# SCH_Arduino_Nano_ESP32_CapibaraZero_2024.net
KiCad netlist of a schematic drawn in EasyEDA
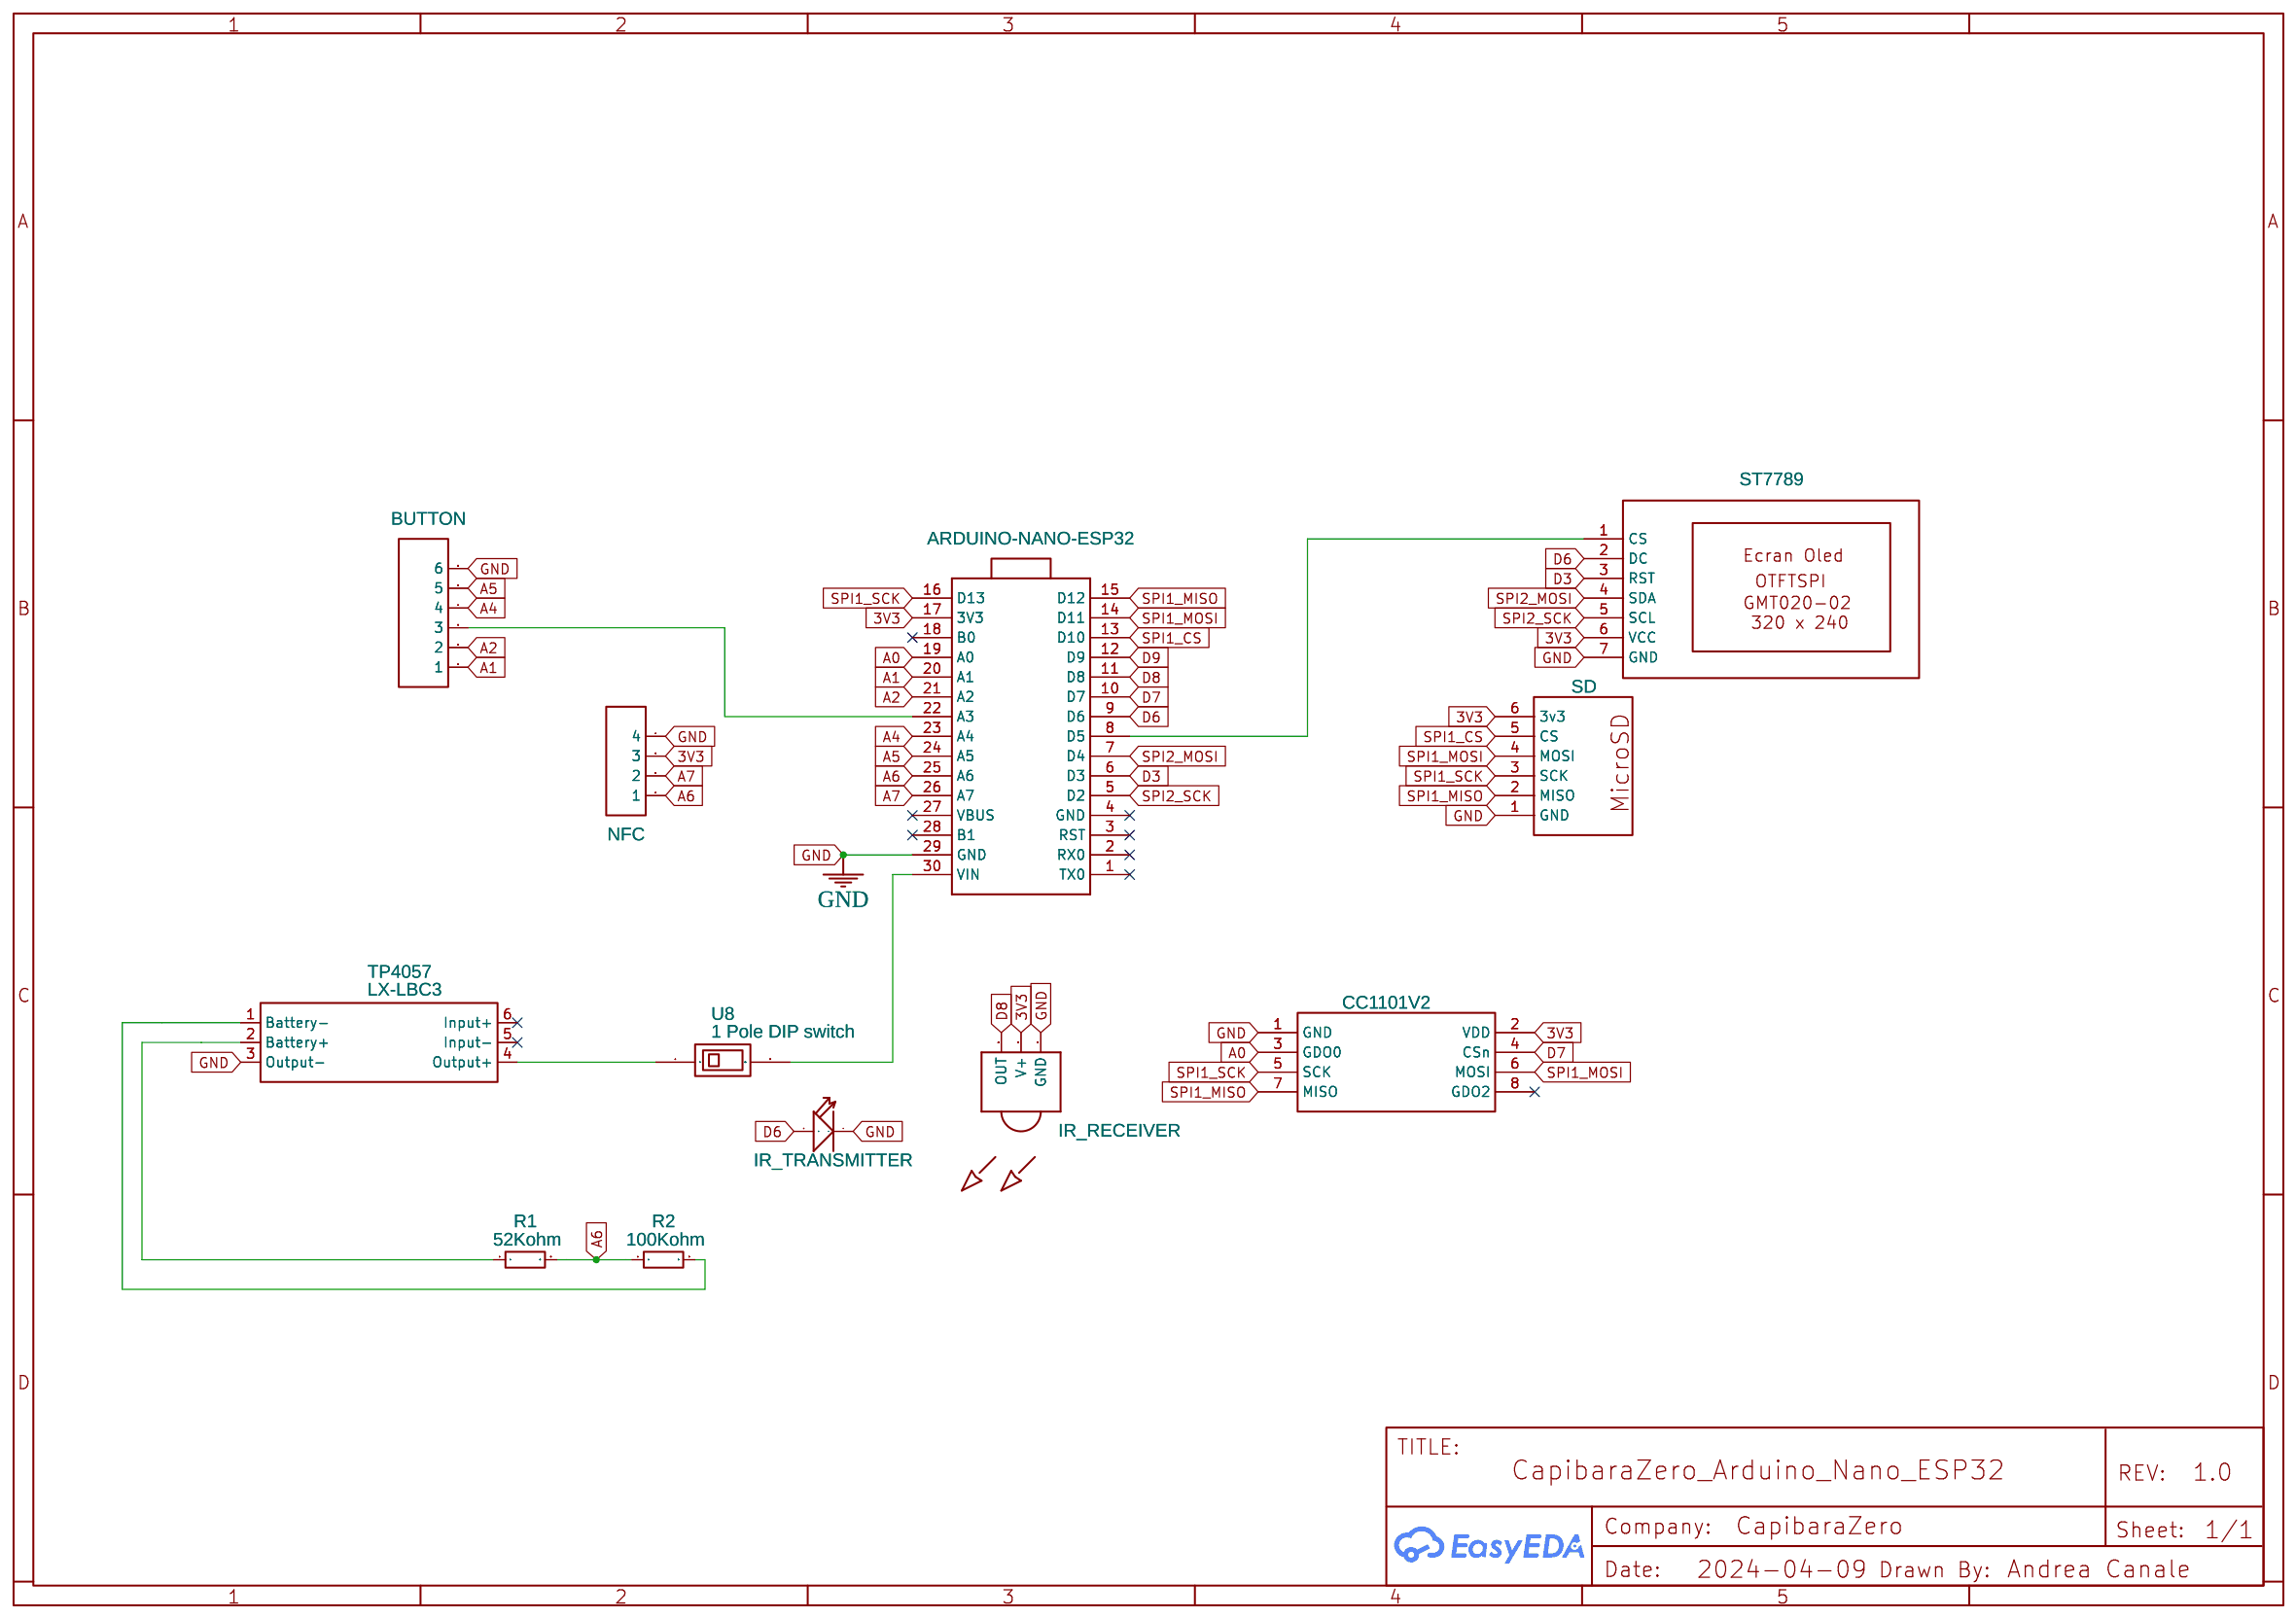
[diagram p0: MainScheme]
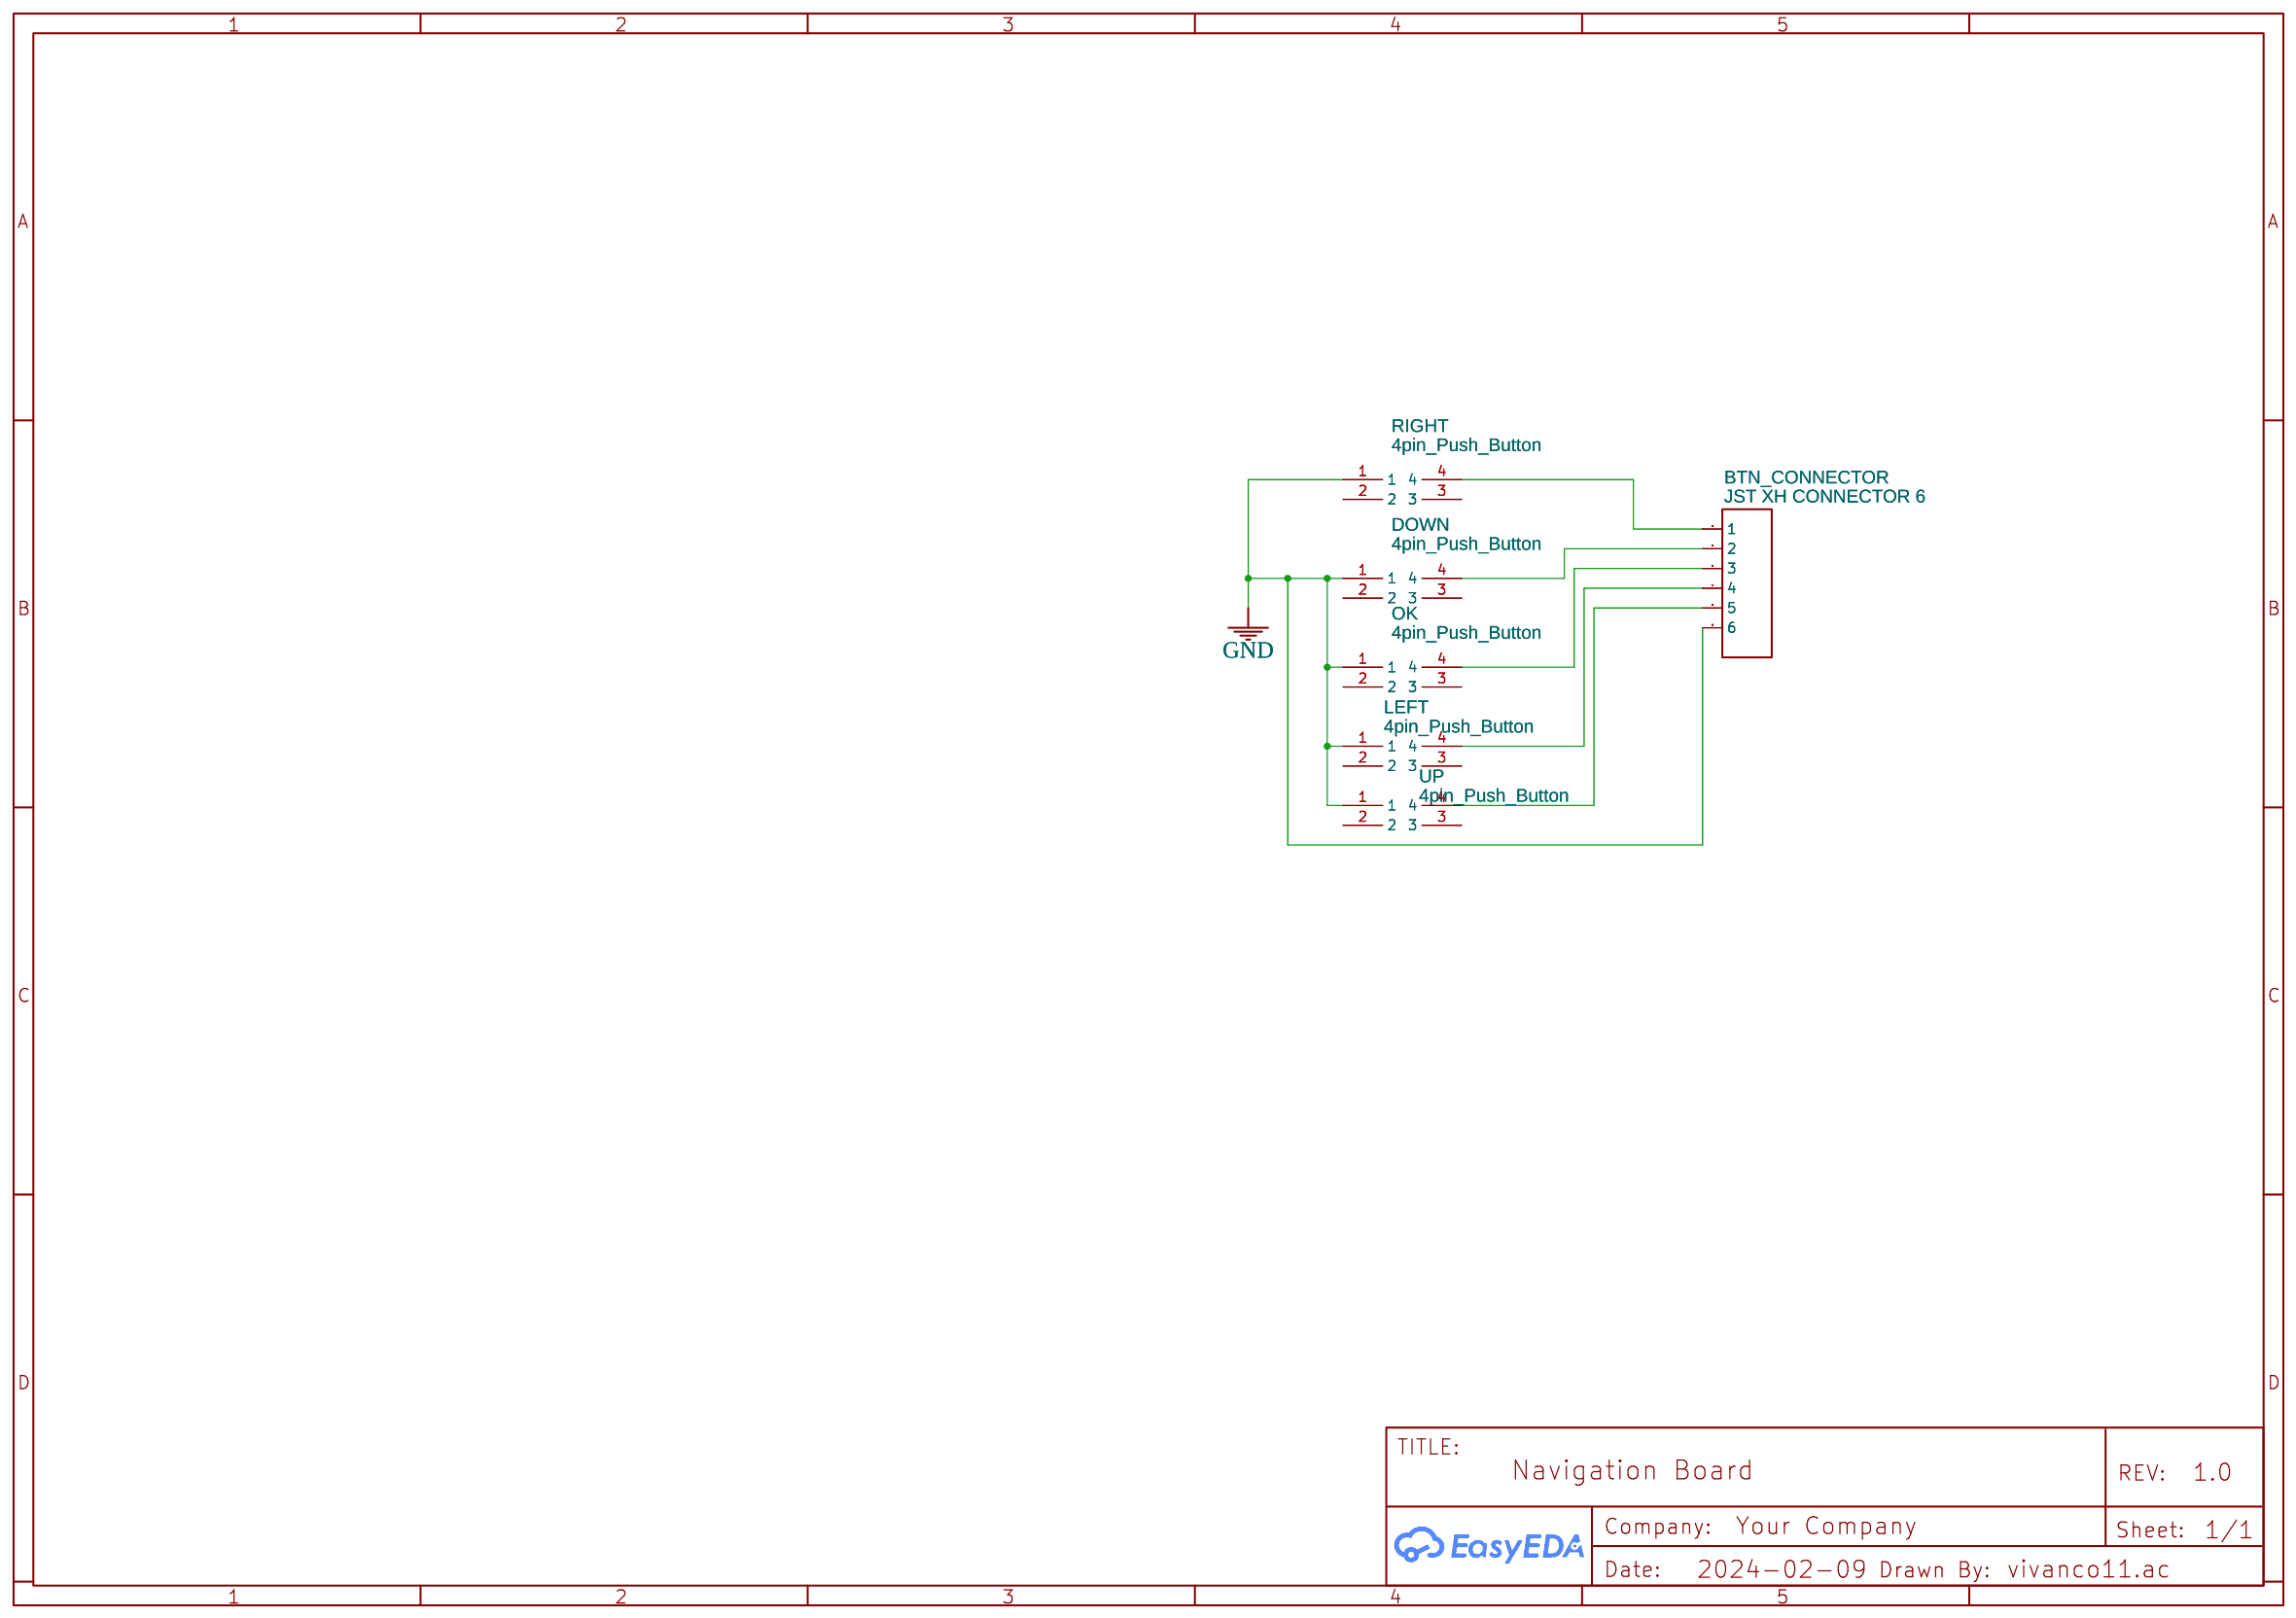
[diagram p1: Navigation_board]

(export (version "E")
  (design (tool "Eeschema 10.0.6"))
  (components
    (comp (ref "ARDUINO-NANO-ESP32")
      (value "ARDUINO-NANO-ESP32")
      (fields (field (name "Manufacturer") "Arduino"))
      (libsource (lib "") (part "ARDUINO-NANO-ESP32"))
    )
    (comp (ref "BUTTON")
      (value "BTN Connector")
      (fields (field (name "Manufacturer Part") "JST_XH CONNECTOR"))
      (libsource (lib "") (part "JST XH CONNECTOR 6"))
    )
    (comp (ref "CC1101V2")
      (value "CC1101 E07-M1101D")
      (fields
        (field (name "Manufacturer Part") "E07-M1101D-SMA")
        (field (name "Manufacturer") "Chengdu Ebyte Electronic Technology Co., Ltd.")
      )
      (libsource (lib "") (part "CC1101 E07-M1101D"))
    )
    (comp (ref "IR_RECEIVER") (value "IR Receiver") (libsource (lib "") (part "IR TRANSMITTER")))
    (comp (ref "IR_TRANSMITTER")
      (value "DIP-IR-LED-940NM(2P-D5MM)")
      (fields (field (name "Manufacturer Part") "IR523B-W60W1"))
      (libsource (lib "") (part "DIP-IR-LED-940NM(2P-D5MM)"))
    )
    (comp (ref "NFC")
      (value "NFC Connector")
      (fields (field (name "Manufacturer Part") "JST_XH CONNECTOR"))
      (libsource (lib "") (part "JST XH CONNECTOR 4"))
    )
    (comp (ref "R1")
      (value "52Kohm")
      (fields
        (field (name "Manufacturer Part") "EWWR0001J20R0T9")
        (field (name "Manufacturer") "ResistorToday")
      )
      (libsource (lib "") (part "Resistor Normal"))
    )
    (comp (ref "R2")
      (value "100Kohm")
      (fields
        (field (name "Manufacturer Part") "EWWR0001J20R0T9")
        (field (name "Manufacturer") "ResistorToday")
      )
      (libsource (lib "") (part "Resistor Normal"))
    )
    (comp (ref "SD") (value "MicroSDSPI") (libsource (lib "") (part "MicroSDSPI")))
    (comp (ref "ST7789")
      (value "ST7789_Display_320x240_SPI")
      (libsource (lib "") (part "ST7789_Display_320x240_SPI"))
    )
    (comp (ref "TP4057") (value "LX-LBC3") (libsource (lib "") (part "LX-LBC3")))
    (comp (ref "U8") (value "1 Pole DIP switch") (libsource (lib "") (part "1 Pole DIP switch")))
    (comp (ref "BTN_CONNECTOR")
      (value "JST XH CONNECTOR 6")
      (fields (field (name "Manufacturer Part") "JST_XH CONNECTOR"))
      (libsource (lib "") (part "JST XH CONNECTOR 6"))
    )
    (comp (ref "DOWN") (value "4pin_Push_Button") (libsource (lib "") (part "4pin_Push_Button_1")))
    (comp (ref "LEFT") (value "4pin_Push_Button") (libsource (lib "") (part "4pin_Push_Button_2")))
    (comp (ref "OK") (value "4pin_Push_Button") (libsource (lib "") (part "4pin_Push_Button_3")))
    (comp (ref "RIGHT") (value "4pin_Push_Button") (libsource (lib "") (part "4pin_Push_Button_4")))
    (comp (ref "UP") (value "4pin_Push_Button") (libsource (lib "") (part "4pin_Push_Button")))
  )
  (nets
    (net (code "1") (name "3V3") (class "Default")
      (node (ref "ARDUINO-NANO-ESP32") (pin "17") (pinfunction "3V3_17") (pintype "unspecified"))
      (node (ref "CC1101V2") (pin "2") (pinfunction "VDD_2") (pintype "unspecified"))
      (node (ref "IR_RECEIVER") (pin "VCC") (pinfunction "V+_VCC") (pintype "unspecified"))
      (node (ref "NFC") (pin "3") (pinfunction "3_3") (pintype "unspecified"))
      (node (ref "SD") (pin "6") (pinfunction "3v3_6") (pintype "unspecified"))
      (node (ref "ST7789") (pin "6") (pinfunction "VCC_6") (pintype "unspecified"))
    )
    (net (code "2") (name "A0") (class "Default")
      (node (ref "ARDUINO-NANO-ESP32") (pin "19") (pinfunction "A0_19") (pintype "unspecified"))
      (node (ref "CC1101V2") (pin "3") (pinfunction "GDO0_3") (pintype "unspecified"))
    )
    (net (code "3") (name "A1") (class "Default")
      (node (ref "ARDUINO-NANO-ESP32") (pin "20") (pinfunction "A1_20") (pintype "unspecified"))
      (node (ref "BUTTON") (pin "1") (pinfunction "1_1") (pintype "unspecified"))
    )
    (net (code "4") (name "A2") (class "Default")
      (node (ref "ARDUINO-NANO-ESP32") (pin "21") (pinfunction "A2_21") (pintype "unspecified"))
      (node (ref "BUTTON") (pin "2") (pinfunction "2_2") (pintype "unspecified"))
    )
    (net (code "5") (name "A4") (class "Default")
      (node (ref "ARDUINO-NANO-ESP32") (pin "23") (pinfunction "A4_23") (pintype "unspecified"))
      (node (ref "BUTTON") (pin "4") (pinfunction "4_4") (pintype "unspecified"))
    )
    (net (code "6") (name "A5") (class "Default")
      (node (ref "ARDUINO-NANO-ESP32") (pin "24") (pinfunction "A5_24") (pintype "unspecified"))
      (node (ref "BUTTON") (pin "5") (pinfunction "5_5") (pintype "unspecified"))
    )
    (net (code "7") (name "A6") (class "Default")
      (node (ref "ARDUINO-NANO-ESP32") (pin "25") (pinfunction "A6_25") (pintype "unspecified"))
      (node (ref "NFC") (pin "1") (pinfunction "1_1") (pintype "unspecified"))
      (node (ref "R1") (pin "2") (pinfunction "2_2") (pintype "unspecified"))
      (node (ref "R2") (pin "1") (pinfunction "1_1") (pintype "unspecified"))
    )
    (net (code "8") (name "A7") (class "Default")
      (node (ref "ARDUINO-NANO-ESP32") (pin "26") (pinfunction "A7_26") (pintype "unspecified"))
      (node (ref "NFC") (pin "2") (pinfunction "2_2") (pintype "unspecified"))
    )
    (net (code "9") (name "D3") (class "Default")
      (node (ref "ARDUINO-NANO-ESP32") (pin "6") (pinfunction "D3_6") (pintype "unspecified"))
      (node (ref "ST7789") (pin "3") (pinfunction "RST_3") (pintype "unspecified"))
    )
    (net (code "10") (name "D6") (class "Default")
      (node (ref "ARDUINO-NANO-ESP32") (pin "9") (pinfunction "D6_9") (pintype "unspecified"))
      (node (ref "IR_TRANSMITTER") (pin "+") (pinfunction "+_+") (pintype "unspecified"))
      (node (ref "ST7789") (pin "2") (pinfunction "DC_2") (pintype "unspecified"))
    )
    (net (code "11") (name "D7") (class "Default")
      (node (ref "ARDUINO-NANO-ESP32") (pin "10") (pinfunction "D7_10") (pintype "unspecified"))
      (node (ref "CC1101V2") (pin "4") (pinfunction "CSn_4") (pintype "unspecified"))
    )
    (net (code "12") (name "D8") (class "Default")
      (node (ref "ARDUINO-NANO-ESP32") (pin "11") (pinfunction "D8_11") (pintype "unspecified"))
      (node (ref "IR_RECEIVER") (pin "OUT") (pinfunction "OUT_OUT") (pintype "unspecified"))
    )
    (net (code "13") (name "D9") (class "Default")
      (node (ref "ARDUINO-NANO-ESP32") (pin "12") (pinfunction "D9_12") (pintype "unspecified"))
    )
    (net (code "14") (name "GND") (class "Default")
      (node (ref "ARDUINO-NANO-ESP32") (pin "29") (pinfunction "GND_29") (pintype "unspecified"))
      (node (ref "BTN_CONNECTOR") (pin "6") (pinfunction "6_6") (pintype "unspecified"))
      (node (ref "BUTTON") (pin "6") (pinfunction "6_6") (pintype "unspecified"))
      (node (ref "CC1101V2") (pin "1") (pinfunction "GND_1") (pintype "unspecified"))
      (node (ref "DOWN") (pin "1") (pinfunction "1_1") (pintype "unspecified"))
      (node (ref "IR_RECEIVER") (pin "GND") (pinfunction "GND_GND") (pintype "unspecified"))
      (node (ref "IR_TRANSMITTER") (pin "-") (pinfunction "-_-") (pintype "unspecified"))
      (node (ref "LEFT") (pin "1") (pinfunction "1_1") (pintype "unspecified"))
      (node (ref "NFC") (pin "4") (pinfunction "4_4") (pintype "unspecified"))
      (node (ref "OK") (pin "1") (pinfunction "1_1") (pintype "unspecified"))
      (node (ref "RIGHT") (pin "1") (pinfunction "1_1") (pintype "unspecified"))
      (node (ref "SD") (pin "1") (pinfunction "GND_1") (pintype "unspecified"))
      (node (ref "ST7789") (pin "7") (pinfunction "GND_7") (pintype "unspecified"))
      (node (ref "TP4057") (pin "3") (pinfunction "Output-_3") (pintype "unspecified"))
      (node (ref "UP") (pin "1") (pinfunction "1_1") (pintype "unspecified"))
    )
    (net (code "15") (name "Net-(ARDUINO-NANO-ESP32-A3)") (class "Default")
      (node (ref "ARDUINO-NANO-ESP32") (pin "22") (pinfunction "A3_22") (pintype "unspecified"))
      (node (ref "BUTTON") (pin "3") (pinfunction "3_3") (pintype "unspecified"))
    )
    (net (code "16") (name "Net-(ARDUINO-NANO-ESP32-D5)") (class "Default")
      (node (ref "ARDUINO-NANO-ESP32") (pin "8") (pinfunction "D5_8") (pintype "unspecified"))
      (node (ref "ST7789") (pin "1") (pinfunction "CS_1") (pintype "unspecified"))
    )
    (net (code "17") (name "Net-(ARDUINO-NANO-ESP32-VIN)") (class "Default")
      (node (ref "ARDUINO-NANO-ESP32") (pin "30") (pinfunction "VIN_30") (pintype "unspecified"))
      (node (ref "U8") (pin "2") (pinfunction "OUT_2") (pintype "unspecified"))
    )
    (net (code "18") (name "Net-(BTN_CONNECTOR-Pad1)") (class "Default")
      (node (ref "BTN_CONNECTOR") (pin "1") (pinfunction "1_1") (pintype "unspecified"))
      (node (ref "RIGHT") (pin "4") (pinfunction "4_4") (pintype "unspecified"))
    )
    (net (code "19") (name "Net-(BTN_CONNECTOR-Pad2)") (class "Default")
      (node (ref "BTN_CONNECTOR") (pin "2") (pinfunction "2_2") (pintype "unspecified"))
      (node (ref "DOWN") (pin "4") (pinfunction "4_4") (pintype "unspecified"))
    )
    (net (code "20") (name "Net-(BTN_CONNECTOR-Pad3)") (class "Default")
      (node (ref "BTN_CONNECTOR") (pin "3") (pinfunction "3_3") (pintype "unspecified"))
      (node (ref "OK") (pin "4") (pinfunction "4_4") (pintype "unspecified"))
    )
    (net (code "21") (name "Net-(BTN_CONNECTOR-Pad4)") (class "Default")
      (node (ref "BTN_CONNECTOR") (pin "4") (pinfunction "4_4") (pintype "unspecified"))
      (node (ref "LEFT") (pin "4") (pinfunction "4_4") (pintype "unspecified"))
    )
    (net (code "22") (name "Net-(BTN_CONNECTOR-Pad5)") (class "Default")
      (node (ref "BTN_CONNECTOR") (pin "5") (pinfunction "5_5") (pintype "unspecified"))
      (node (ref "UP") (pin "4") (pinfunction "4_4") (pintype "unspecified"))
    )
    (net (code "23") (name "Net-(TP4057-Battery+)") (class "Default")
      (node (ref "R1") (pin "1") (pinfunction "1_1") (pintype "unspecified"))
      (node (ref "TP4057") (pin "2") (pinfunction "Battery+_2") (pintype "unspecified"))
    )
    (net (code "24") (name "Net-(TP4057-Battery-)") (class "Default")
      (node (ref "R2") (pin "2") (pinfunction "2_2") (pintype "unspecified"))
      (node (ref "TP4057") (pin "1") (pinfunction "Battery-_1") (pintype "unspecified"))
    )
    (net (code "25") (name "Net-(TP4057-Output+)") (class "Default")
      (node (ref "TP4057") (pin "4") (pinfunction "Output+_4") (pintype "unspecified"))
      (node (ref "U8") (pin "1") (pinfunction "IN_1") (pintype "unspecified"))
    )
    (net (code "26") (name "SPI1_CS") (class "Default")
      (node (ref "ARDUINO-NANO-ESP32") (pin "13") (pinfunction "D10_13") (pintype "unspecified"))
      (node (ref "SD") (pin "5") (pinfunction "CS_5") (pintype "unspecified"))
    )
    (net (code "27") (name "SPI1_MISO") (class "Default")
      (node (ref "ARDUINO-NANO-ESP32") (pin "15") (pinfunction "D12_15") (pintype "unspecified"))
      (node (ref "CC1101V2") (pin "7") (pinfunction "MISO_7") (pintype "unspecified"))
      (node (ref "SD") (pin "2") (pinfunction "MISO_2") (pintype "unspecified"))
    )
    (net (code "28") (name "SPI1_MOSI") (class "Default")
      (node (ref "ARDUINO-NANO-ESP32") (pin "14") (pinfunction "D11_14") (pintype "unspecified"))
      (node (ref "CC1101V2") (pin "6") (pinfunction "MOSI_6") (pintype "unspecified"))
      (node (ref "SD") (pin "4") (pinfunction "MOSI_4") (pintype "unspecified"))
    )
    (net (code "29") (name "SPI1_SCK") (class "Default")
      (node (ref "ARDUINO-NANO-ESP32") (pin "16") (pinfunction "D13_16") (pintype "unspecified"))
      (node (ref "CC1101V2") (pin "5") (pinfunction "SCK_5") (pintype "unspecified"))
      (node (ref "SD") (pin "3") (pinfunction "SCK_3") (pintype "unspecified"))
    )
    (net (code "30") (name "SPI2_MOSI") (class "Default")
      (node (ref "ARDUINO-NANO-ESP32") (pin "7") (pinfunction "D4_7") (pintype "unspecified"))
      (node (ref "ST7789") (pin "4") (pinfunction "SDA_4") (pintype "unspecified"))
    )
    (net (code "31") (name "SPI2_SCK") (class "Default")
      (node (ref "ARDUINO-NANO-ESP32") (pin "5") (pinfunction "D2_5") (pintype "unspecified"))
      (node (ref "ST7789") (pin "5") (pinfunction "SCL_5") (pintype "unspecified"))
    )
    (net (code "32") (name "unconnected-(ARDUINO-NANO-ESP32-B0-Pad18)") (class "Default")
      (node (ref "ARDUINO-NANO-ESP32") (pin "18") (pinfunction "B0_18") (pintype "unspecified+no_connect"))
    )
    (net (code "33") (name "unconnected-(ARDUINO-NANO-ESP32-B1-Pad28)") (class "Default")
      (node (ref "ARDUINO-NANO-ESP32") (pin "28") (pinfunction "B1_28") (pintype "unspecified+no_connect"))
    )
    (net (code "34") (name "unconnected-(ARDUINO-NANO-ESP32-GND-Pad4)") (class "Default")
      (node (ref "ARDUINO-NANO-ESP32") (pin "4") (pinfunction "GND_4") (pintype "unspecified+no_connect"))
    )
    (net (code "35") (name "unconnected-(ARDUINO-NANO-ESP32-RST-Pad3)") (class "Default")
      (node (ref "ARDUINO-NANO-ESP32") (pin "3") (pinfunction "RST_3") (pintype "unspecified+no_connect"))
    )
    (net (code "36") (name "unconnected-(ARDUINO-NANO-ESP32-RX0-Pad2)") (class "Default")
      (node (ref "ARDUINO-NANO-ESP32") (pin "2") (pinfunction "RX0_2") (pintype "unspecified+no_connect"))
    )
    (net (code "37") (name "unconnected-(ARDUINO-NANO-ESP32-TX0-Pad1)") (class "Default")
      (node (ref "ARDUINO-NANO-ESP32") (pin "1") (pinfunction "TX0_1") (pintype "unspecified+no_connect"))
    )
    (net (code "38") (name "unconnected-(ARDUINO-NANO-ESP32-VBUS-Pad27)") (class "Default")
      (node (ref "ARDUINO-NANO-ESP32") (pin "27") (pinfunction "VBUS_27") (pintype "unspecified+no_connect"))
    )
    (net (code "39") (name "unconnected-(CC1101V2-GDO2-Pad8)") (class "Default")
      (node (ref "CC1101V2") (pin "8") (pinfunction "GDO2_8") (pintype "unspecified+no_connect"))
    )
    (net (code "40") (name "unconnected-(DOWN-Pad2)") (class "Default")
      (node (ref "DOWN") (pin "2") (pinfunction "2_2") (pintype "unspecified"))
    )
    (net (code "41") (name "unconnected-(DOWN-Pad3)") (class "Default")
      (node (ref "DOWN") (pin "3") (pinfunction "3_3") (pintype "unspecified"))
    )
    (net (code "42") (name "unconnected-(LEFT-Pad2)") (class "Default")
      (node (ref "LEFT") (pin "2") (pinfunction "2_2") (pintype "unspecified"))
    )
    (net (code "43") (name "unconnected-(LEFT-Pad3)") (class "Default")
      (node (ref "LEFT") (pin "3") (pinfunction "3_3") (pintype "unspecified"))
    )
    (net (code "44") (name "unconnected-(OK-Pad2)") (class "Default")
      (node (ref "OK") (pin "2") (pinfunction "2_2") (pintype "unspecified"))
    )
    (net (code "45") (name "unconnected-(OK-Pad3)") (class "Default")
      (node (ref "OK") (pin "3") (pinfunction "3_3") (pintype "unspecified"))
    )
    (net (code "46") (name "unconnected-(RIGHT-Pad2)") (class "Default")
      (node (ref "RIGHT") (pin "2") (pinfunction "2_2") (pintype "unspecified"))
    )
    (net (code "47") (name "unconnected-(RIGHT-Pad3)") (class "Default")
      (node (ref "RIGHT") (pin "3") (pinfunction "3_3") (pintype "unspecified"))
    )
    (net (code "48") (name "unconnected-(TP4057-Input+-Pad6)") (class "Default")
      (node (ref "TP4057") (pin "6") (pinfunction "Input+_6") (pintype "unspecified+no_connect"))
    )
    (net (code "49") (name "unconnected-(TP4057-Input--Pad5)") (class "Default")
      (node (ref "TP4057") (pin "5") (pinfunction "Input-_5") (pintype "unspecified+no_connect"))
    )
    (net (code "50") (name "unconnected-(UP-Pad2)") (class "Default")
      (node (ref "UP") (pin "2") (pinfunction "2_2") (pintype "unspecified"))
    )
    (net (code "51") (name "unconnected-(UP-Pad3)") (class "Default")
      (node (ref "UP") (pin "3") (pinfunction "3_3") (pintype "unspecified"))
    )
  )
)
